# Motor_Controller.net
KiCad netlist of a schematic drawn in Altium Designer
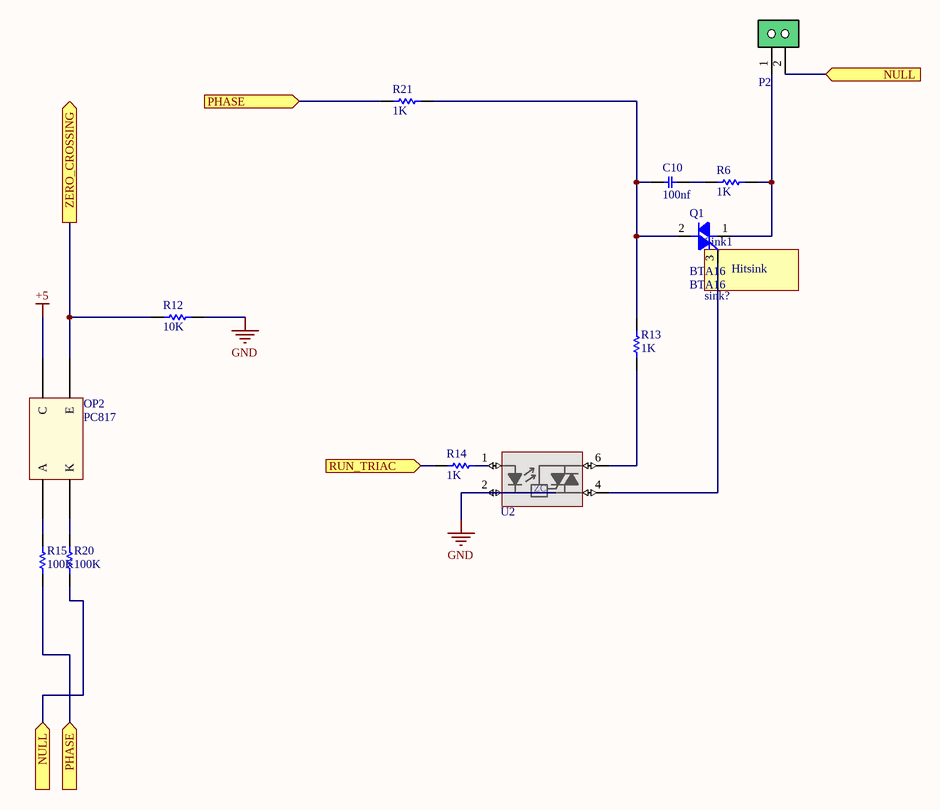
[diagram p0: Motor_Controller.SchDoc]

(export (version "E")
  (design (tool "Eeschema 10.0.6"))
  (components
    (comp (ref "C10")
      (value "100nf")
      (footprint "C_PLY_13X5")
      (description "Capacitor Polyester THD")
      (libsource (lib "Capacitor") (part "Capacitor Polyester THD"))
    )
    (comp (ref "OP2")
      (value "PC817")
      (footprint "PC817 SMD")
      (description "PC817 optocpler")
      (libsource (lib "IC") (part "PC817"))
    )
    (comp (ref "P2")
      (value "Phoenix 2")
      (footprint "PRKR2A")
      (libsource (lib "Connector") (part "Phoenix 2"))
    )
    (comp (ref "Q1")
      (value "BTA16")
      (footprint "TO220")
      (description "Triac, 800V, 16A, TO-220")
      (fields (field (name "ALTIUM_VALUE") "BTA16"))
      (libsource (lib "Triac") (part "BTA16"))
    )
    (comp (ref "R6")
      (value "1K")
      (footprint "R05W_AX05")
      (description "Resistor THD")
      (libsource (lib "Resistor") (part "Resistor THD"))
    )
    (comp (ref "R12")
      (value "10K")
      (footprint "SMD-1206-RES")
      (description "Resistor SMD 1206")
      (libsource (lib "Resistor") (part "Resistor SMD 1206"))
    )
    (comp (ref "R13")
      (value "1K")
      (footprint "SMD-1206-RES")
      (description "Resistor SMD 1206")
      (libsource (lib "Resistor") (part "Resistor SMD 1206"))
    )
    (comp (ref "R14")
      (value "1K")
      (footprint "SMD-1206-RES")
      (description "Resistor SMD 1206")
      (libsource (lib "Resistor") (part "Resistor SMD 1206"))
    )
    (comp (ref "R15")
      (value "100K")
      (footprint "R2W_AX08")
      (description "Resistor THD")
      (libsource (lib "Resistor") (part "Resistor THD"))
    )
    (comp (ref "R20")
      (value "100K")
      (footprint "R2W_AX08")
      (description "Resistor THD")
      (libsource (lib "Resistor") (part "Resistor THD"))
    )
    (comp (ref "R21")
      (value "1K")
      (footprint "SMD-1206-RES")
      (description "Resistor SMD 1206")
      (libsource (lib "Resistor") (part "Resistor SMD 1206"))
    )
    (comp (ref "Sink1")
      (value "sink?")
      (footprint "heatsink (4)")
      (libsource (lib "Heatsink") (part "Hitsink"))
    )
    (comp (ref "U2") (value "MOC30XX") (footprint "DIP-6 white") (libsource (lib "IC") (part "MOC30XX")))
  )
  (nets
    (net (code "1") (name "+5") (class "Default")
      (node (ref "OP2") (pin "4") (pinfunction "C_4") (pintype "passive"))
    )
    (net (code "2") (name "/NULL") (class "Default")
      (node (ref "P2") (pin "2") (pinfunction "2_2") (pintype "passive"))
      (node (ref "R20") (pin "1") (pinfunction "1_1") (pintype "passive"))
    )
    (net (code "3") (name "/PHASE") (class "Default")
      (node (ref "R15") (pin "1") (pinfunction "1_1") (pintype "passive"))
      (node (ref "R21") (pin "1") (pinfunction "1_1") (pintype "passive"))
    )
    (net (code "4") (name "/RUN_TRIAC") (class "Default")
      (node (ref "R14") (pin "1") (pinfunction "1_1") (pintype "passive"))
    )
    (net (code "5") (name "/ZERO_CROSSING") (class "Default")
      (node (ref "OP2") (pin "3") (pinfunction "E_3") (pintype "passive"))
      (node (ref "R12") (pin "1") (pinfunction "1_1") (pintype "passive"))
    )
    (net (code "6") (name "GND") (class "Default")
      (node (ref "R12") (pin "2") (pinfunction "2_2") (pintype "passive"))
      (node (ref "U2") (pin "2") (pinfunction "K_2") (pintype "bidirectional"))
    )
    (net (code "7") (name "Net-(C10-Pad2)") (class "Default")
      (node (ref "C10") (pin "2") (pinfunction "2_2") (pintype "passive"))
      (node (ref "R6") (pin "1") (pinfunction "1_1") (pintype "passive"))
    )
    (net (code "8") (name "Net-(OP2-A)") (class "Default")
      (node (ref "OP2") (pin "1") (pinfunction "A_1") (pintype "passive"))
      (node (ref "R15") (pin "2") (pinfunction "2_2") (pintype "passive"))
    )
    (net (code "9") (name "Net-(OP2-K)") (class "Default")
      (node (ref "OP2") (pin "2") (pinfunction "K_2") (pintype "passive"))
      (node (ref "R20") (pin "2") (pinfunction "2_2") (pintype "passive"))
    )
    (net (code "10") (name "Net-(Q1-G)") (class "Default")
      (node (ref "Q1") (pin "3") (pinfunction "G_3") (pintype "passive"))
      (node (ref "U2") (pin "4") (pinfunction "T2_4") (pintype "bidirectional"))
    )
    (net (code "11") (name "Net-(Q1-T1)") (class "Default")
      (node (ref "P2") (pin "1") (pinfunction "1_1") (pintype "passive"))
      (node (ref "Q1") (pin "1") (pinfunction "T1_1") (pintype "passive"))
      (node (ref "R6") (pin "2") (pinfunction "2_2") (pintype "passive"))
    )
    (net (code "12") (name "Net-(Q1-T2)") (class "Default")
      (node (ref "C10") (pin "1") (pinfunction "1_1") (pintype "passive"))
      (node (ref "Q1") (pin "2") (pinfunction "T2_2") (pintype "passive"))
      (node (ref "R13") (pin "2") (pinfunction "2_2") (pintype "passive"))
      (node (ref "R21") (pin "2") (pinfunction "2_2") (pintype "passive"))
    )
    (net (code "13") (name "Net-(U2-A)") (class "Default")
      (node (ref "R14") (pin "2") (pinfunction "2_2") (pintype "passive"))
      (node (ref "U2") (pin "1") (pinfunction "A_1") (pintype "bidirectional"))
    )
    (net (code "14") (name "Net-(U2-T1)") (class "Default")
      (node (ref "R13") (pin "1") (pinfunction "1_1") (pintype "passive"))
      (node (ref "U2") (pin "6") (pinfunction "T1_6") (pintype "bidirectional"))
    )
  )
)
